# Hypnos_V3_2.net
KiCad netlist of a schematic drawn in EAGLE
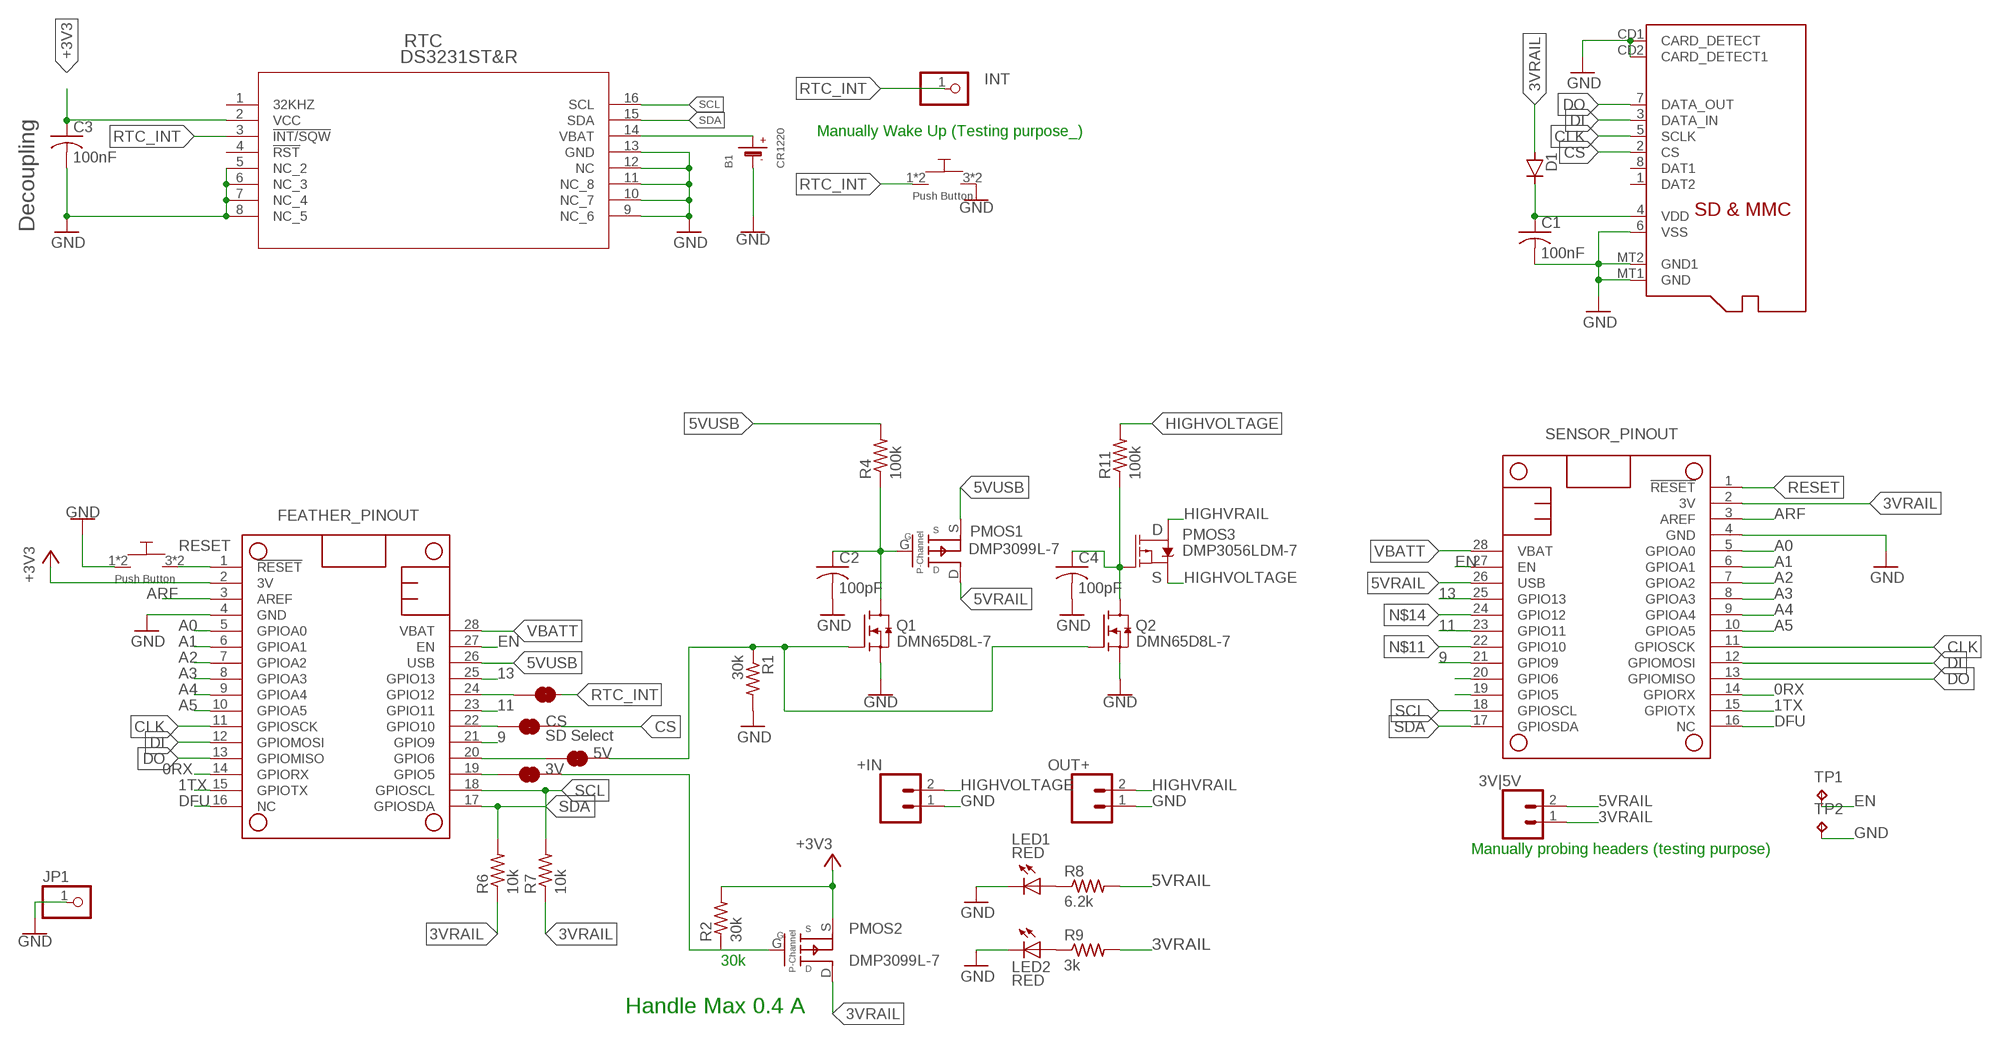
[diagram p0: schematic, sheet 1]

(export (version "E")
  (design (tool "Eeschema 10.0.6"))
  (components
    (comp (ref "+IN")
      (value "HIGHV-IN")
      (footprint "eagle-import:1X02_NO_SILK")
      (libsource (lib "eagle-import") (part "CONN_021X02_NO_SILK"))
    )
    (comp (ref "3V")
      (value "JUMPER-SMT_2_NC_TRACE_SILK")
      (footprint "eagle-import:SMT-JUMPER_2_NC_TRACE_SILK")
      (libsource (lib "eagle-import") (part "JUMPER-SMT_2_NC_TRACE_SILK"))
    )
    (comp (ref "3V|5V")
      (value "CONN_021X02_NO_SILK")
      (footprint "eagle-import:1X02_NO_SILK")
      (libsource (lib "eagle-import") (part "CONN_021X02_NO_SILK"))
    )
    (comp (ref "5V")
      (value "JUMPER-SMT_2_NC_TRACE_SILK")
      (footprint "eagle-import:SMT-JUMPER_2_NC_TRACE_SILK")
      (libsource (lib "eagle-import") (part "JUMPER-SMT_2_NC_TRACE_SILK"))
    )
    (comp (ref "B1")
      (value "CR1220")
      (footprint "eagle-import:CR1220")
      (libsource (lib "eagle-import") (part "BATTERYCR1220_SMT"))
    )
    (comp (ref "C1")
      (value "100nF")
      (footprint "eagle-import:C1206")
      (libsource (lib "eagle-import") (part "C-USC1206"))
    )
    (comp (ref "C2")
      (value "100pF")
      (footprint "eagle-import:C0805")
      (libsource (lib "eagle-import") (part "resistor_348_C-USC0805"))
    )
    (comp (ref "C3")
      (value "100nF")
      (footprint "eagle-import:C1206")
      (libsource (lib "eagle-import") (part "C-USC1206"))
    )
    (comp (ref "C4")
      (value "100pF")
      (footprint "eagle-import:C0805")
      (libsource (lib "eagle-import") (part "resistor_348_C-USC0805"))
    )
    (comp (ref "CS")
      (value "SD Select")
      (footprint "eagle-import:SMT-JUMPER_2_NC_TRACE_SILK")
      (libsource (lib "eagle-import") (part "JUMPER-SMT_2_NC_TRACE_SILK"))
    )
    (comp (ref "D1")
      (value "D-SOD123")
      (footprint "eagle-import:SOD123")
      (libsource (lib "eagle-import") (part "D-SOD123"))
    )
    (comp (ref "FEATHERWING")
      (value "SENSOR_PINOUT")
      (footprint "eagle-import:FEATHERWING")
      (libsource (lib "eagle-import") (part "powerboard_FEATHERWING"))
    )
    (comp (ref "INT")
      (value "PINHD-1X1CB")
      (footprint "eagle-import:1X01-CLEANBIG")
      (libsource (lib "eagle-import") (part "PINHD-1X1CB"))
    )
    (comp (ref "JP1")
      (value "PINHD-1X1CB")
      (footprint "eagle-import:1X01-CLEANBIG")
      (libsource (lib "eagle-import") (part "PINHD-1X1CB"))
    )
    (comp (ref "LED1")
      (value "RED")
      (footprint "eagle-import:CHIPLED_0805")
      (libsource (lib "eagle-import") (part "LEDCHIPLED_0805"))
    )
    (comp (ref "LED2")
      (value "RED")
      (footprint "eagle-import:CHIPLED_0805")
      (libsource (lib "eagle-import") (part "LEDCHIPLED_0805"))
    )
    (comp (ref "MICROSD")
      (value "MICROSD")
      (footprint "eagle-import:MICROSD")
      (libsource (lib "eagle-import") (part "MICROSD"))
    )
    (comp (ref "MS2")
      (value "FEATHER_PINOUT")
      (footprint "eagle-import:FEATHERWING")
      (libsource (lib "eagle-import") (part "FEATHERWING"))
    )
    (comp (ref "OUT+")
      (value "HIGHV-OUT")
      (footprint "eagle-import:1X02_NO_SILK")
      (libsource (lib "eagle-import") (part "CONN_021X02_NO_SILK"))
    )
    (comp (ref "PMOS1")
      (value "DMP3099L-7")
      (footprint "eagle-import:SOT-23-3")
      (libsource (lib "eagle-import") (part "SSM3J3228R"))
    )
    (comp (ref "PMOS2")
      (value "DMP3099L-7")
      (footprint "eagle-import:SOT-23-3")
      (libsource (lib "eagle-import") (part "SSM3J3228R"))
    )
    (comp (ref "PMOS3")
      (value "DMP3056LDM-7")
      (footprint "eagle-import:SOT23-6")
      (libsource (lib "eagle-import") (part "P-MOSFET"))
    )
    (comp (ref "Q1")
      (value "DMN65D8L-7")
      (footprint "eagle-import:SOT23-S")
      (libsource (lib "eagle-import") (part "NMOS"))
    )
    (comp (ref "Q2")
      (value "DMN65D8L-7")
      (footprint "eagle-import:SOT23-S")
      (libsource (lib "eagle-import") (part "NMOS"))
    )
    (comp (ref "R1")
      (value "30k")
      (footprint "eagle-import:RES_1206")
      (fields
        (field (name "DIGIKEY_PART_NUMBER") "WSLP-.05TR-ND")
        (field (name "MANUFACTURER") "Vishay Dale")
        (field (name "MPN") "WSLP1206R0500FEA")
        (field (name "CREATED_BY") "PCBLayout.com")
      )
      (libsource (lib "eagle-import") (part "WSLP1206R0500FEA"))
    )
    (comp (ref "R2")
      (value "30k")
      (footprint "eagle-import:RES_1206")
      (fields
        (field (name "DIGIKEY_PART_NUMBER") "WSLP-.05TR-ND")
        (field (name "MANUFACTURER") "Vishay Dale")
        (field (name "MPN") "WSLP1206R0500FEA")
        (field (name "CREATED_BY") "PCBLayout.com")
      )
      (libsource (lib "eagle-import") (part "WSLP1206R0500FEA"))
    )
    (comp (ref "R4")
      (value "100k")
      (footprint "eagle-import:RES_1206")
      (fields
        (field (name "DIGIKEY_PART_NUMBER") "WSLP-.05TR-ND")
        (field (name "MANUFACTURER") "Vishay Dale")
        (field (name "MPN") "WSLP1206R0500FEA")
        (field (name "CREATED_BY") "PCBLayout.com")
      )
      (libsource (lib "eagle-import") (part "WSLP1206R0500FEA"))
    )
    (comp (ref "R6")
      (value "10k")
      (footprint "eagle-import:RES_1206")
      (fields
        (field (name "DIGIKEY_PART_NUMBER") "WSLP-.05TR-ND")
        (field (name "MANUFACTURER") "Vishay Dale")
        (field (name "MPN") "WSLP1206R0500FEA")
        (field (name "CREATED_BY") "PCBLayout.com")
      )
      (libsource (lib "eagle-import") (part "WSLP1206R0500FEA"))
    )
    (comp (ref "R7")
      (value "10k")
      (footprint "eagle-import:RES_1206")
      (fields
        (field (name "DIGIKEY_PART_NUMBER") "WSLP-.05TR-ND")
        (field (name "MANUFACTURER") "Vishay Dale")
        (field (name "MPN") "WSLP1206R0500FEA")
        (field (name "CREATED_BY") "PCBLayout.com")
      )
      (libsource (lib "eagle-import") (part "WSLP1206R0500FEA"))
    )
    (comp (ref "R8")
      (value "6.2k")
      (footprint "eagle-import:RES_1206")
      (fields
        (field (name "DIGIKEY_PART_NUMBER") "WSLP-.05TR-ND")
        (field (name "MANUFACTURER") "Vishay Dale")
        (field (name "MPN") "WSLP1206R0500FEA")
        (field (name "CREATED_BY") "PCBLayout.com")
      )
      (libsource (lib "eagle-import") (part "WSLP1206R0500FEA"))
    )
    (comp (ref "R9")
      (value "3k")
      (footprint "eagle-import:RES_1206")
      (fields
        (field (name "DIGIKEY_PART_NUMBER") "WSLP-.05TR-ND")
        (field (name "MANUFACTURER") "Vishay Dale")
        (field (name "MPN") "WSLP1206R0500FEA")
        (field (name "CREATED_BY") "PCBLayout.com")
      )
      (libsource (lib "eagle-import") (part "WSLP1206R0500FEA"))
    )
    (comp (ref "R11")
      (value "100k")
      (footprint "eagle-import:RES_1206")
      (fields
        (field (name "DIGIKEY_PART_NUMBER") "WSLP-.05TR-ND")
        (field (name "MANUFACTURER") "Vishay Dale")
        (field (name "MPN") "WSLP1206R0500FEA")
        (field (name "CREATED_BY") "PCBLayout.com")
      )
      (libsource (lib "eagle-import") (part "WSLP1206R0500FEA"))
    )
    (comp (ref "RTC")
      (value "DS3231ST&R")
      (footprint "eagle-import:21-0042B_16")
      (fields (field (name "MANUFACTURER_PART_NUMBER") "DS3231S#T&R"))
      (libsource (lib "eagle-import") (part "DS3231ST&R"))
    )
    (comp (ref "RTC_INT")
      (value "JUMPER-SMT_2_NC_TRACE_SILK")
      (footprint "eagle-import:SMT-JUMPER_2_NC_TRACE_SILK")
      (libsource (lib "eagle-import") (part "JUMPER-SMT_2_NC_TRACE_SILK"))
    )
    (comp (ref "TP1")
      (value "TPTP16R")
      (footprint "eagle-import:TP16R")
      (libsource (lib "eagle-import") (part "TPTP16R"))
    )
    (comp (ref "TP2")
      (value "TPTP16R")
      (footprint "eagle-import:TP16R")
      (libsource (lib "eagle-import") (part "TPTP16R"))
    )
    (comp (ref "U$1")
      (value "PUSH_BUTTON")
      (footprint "eagle-import:PUSHBUTTON_SMD")
      (libsource (lib "eagle-import") (part "PUSH_BUTTON"))
    )
    (comp (ref "U$2")
      (value "PUSH_BUTTON")
      (footprint "eagle-import:PUSHBUTTON_SMD")
      (libsource (lib "eagle-import") (part "PUSH_BUTTON"))
    )
  )
  (nets
    (net (code "1") (name "+3V3") (class "Default")
      (node (ref "C3") (pin "1") (pinfunction "1_1") (pintype "passive"))
      (node (ref "MS2") (pin "2") (pinfunction "3V_2") (pintype "power_in"))
      (node (ref "PMOS2") (pin "S") (pinfunction "S_S") (pintype "bidirectional"))
      (node (ref "R2") (pin "2") (pinfunction "2_2") (pintype "passive"))
      (node (ref "RTC") (pin "2") (pinfunction "VCC_2") (pintype "power_in"))
    )
    (net (code "2") (name "/0RX") (class "Default")
      (node (ref "FEATHERWING") (pin "14") (pinfunction "GPIORX_14") (pintype "bidirectional"))
      (node (ref "MS2") (pin "14") (pinfunction "GPIORX_14") (pintype "bidirectional"))
    )
    (net (code "3") (name "/1TX") (class "Default")
      (node (ref "FEATHERWING") (pin "15") (pinfunction "GPIOTX_15") (pintype "bidirectional"))
      (node (ref "MS2") (pin "15") (pinfunction "GPIOTX_15") (pintype "bidirectional"))
    )
    (net (code "4") (name "/9") (class "Default")
      (node (ref "FEATHERWING") (pin "21") (pinfunction "GPIO9_21") (pintype "bidirectional"))
      (node (ref "MS2") (pin "21") (pinfunction "GPIO9_21") (pintype "bidirectional"))
    )
    (net (code "5") (name "/11") (class "Default")
      (node (ref "FEATHERWING") (pin "23") (pinfunction "GPIO11_23") (pintype "bidirectional"))
      (node (ref "MS2") (pin "23") (pinfunction "GPIO11_23") (pintype "bidirectional"))
    )
    (net (code "6") (name "/13") (class "Default")
      (node (ref "FEATHERWING") (pin "25") (pinfunction "GPIO13_25") (pintype "bidirectional"))
      (node (ref "MS2") (pin "25") (pinfunction "GPIO13_25") (pintype "bidirectional"))
    )
    (net (code "7") (name "/A0") (class "Default")
      (node (ref "FEATHERWING") (pin "5") (pinfunction "GPIOA0_5") (pintype "bidirectional"))
      (node (ref "MS2") (pin "5") (pinfunction "GPIOA0_5") (pintype "bidirectional"))
    )
    (net (code "8") (name "/A1") (class "Default")
      (node (ref "FEATHERWING") (pin "6") (pinfunction "GPIOA1_6") (pintype "bidirectional"))
      (node (ref "MS2") (pin "6") (pinfunction "GPIOA1_6") (pintype "bidirectional"))
    )
    (net (code "9") (name "/A2") (class "Default")
      (node (ref "FEATHERWING") (pin "7") (pinfunction "GPIOA2_7") (pintype "bidirectional"))
      (node (ref "MS2") (pin "7") (pinfunction "GPIOA2_7") (pintype "bidirectional"))
    )
    (net (code "10") (name "/A3") (class "Default")
      (node (ref "FEATHERWING") (pin "8") (pinfunction "GPIOA3_8") (pintype "bidirectional"))
      (node (ref "MS2") (pin "8") (pinfunction "GPIOA3_8") (pintype "bidirectional"))
    )
    (net (code "11") (name "/A4") (class "Default")
      (node (ref "FEATHERWING") (pin "9") (pinfunction "GPIOA4_9") (pintype "bidirectional"))
      (node (ref "MS2") (pin "9") (pinfunction "GPIOA4_9") (pintype "bidirectional"))
    )
    (net (code "12") (name "/A5") (class "Default")
      (node (ref "FEATHERWING") (pin "10") (pinfunction "GPIOA5_10") (pintype "bidirectional"))
      (node (ref "MS2") (pin "10") (pinfunction "GPIOA5_10") (pintype "bidirectional"))
    )
    (net (code "13") (name "/ARF") (class "Default")
      (node (ref "FEATHERWING") (pin "3") (pinfunction "AREF_3") (pintype "passive"))
      (node (ref "MS2") (pin "3") (pinfunction "AREF_3") (pintype "passive"))
    )
    (net (code "14") (name "/DFU") (class "Default")
      (node (ref "FEATHERWING") (pin "16") (pinfunction "NC_16") (pintype "passive"))
      (node (ref "MS2") (pin "16") (pinfunction "NC_16") (pintype "passive"))
    )
    (net (code "15") (name "/EN") (class "Default")
      (node (ref "FEATHERWING") (pin "27") (pinfunction "EN_27") (pintype "passive"))
      (node (ref "MS2") (pin "27") (pinfunction "EN_27") (pintype "passive"))
      (node (ref "TP1") (pin "TP") (pinfunction "TP_TP") (pintype "input"))
    )
    (net (code "16") (name "/HIGHVRAIL") (class "Default")
      (node (ref "OUT+") (pin "2") (pinfunction "2_2") (pintype "passive"))
      (node (ref "PMOS3") (pin "1") (pinfunction "D_1") (pintype "bidirectional"))
      (node (ref "PMOS3") (pin "2") (pinfunction "D_2") (pintype "bidirectional"))
      (node (ref "PMOS3") (pin "5") (pinfunction "D_5") (pintype "bidirectional"))
      (node (ref "PMOS3") (pin "6") (pinfunction "D_6") (pintype "bidirectional"))
    )
    (net (code "17") (name "3VRAIL") (class "Default")
      (node (ref "3V|5V") (pin "1") (pinfunction "1_1") (pintype "passive"))
      (node (ref "D1") (pin "2") (pinfunction "A_2") (pintype "passive"))
      (node (ref "FEATHERWING") (pin "2") (pinfunction "3V_2") (pintype "power_in"))
      (node (ref "PMOS2") (pin "D") (pinfunction "D_D") (pintype "bidirectional"))
      (node (ref "R6") (pin "1") (pinfunction "1_1") (pintype "passive"))
      (node (ref "R7") (pin "1") (pinfunction "1_1") (pintype "passive"))
      (node (ref "R9") (pin "2") (pinfunction "2_2") (pintype "passive"))
    )
    (net (code "18") (name "5VRAIL") (class "Default")
      (node (ref "3V|5V") (pin "2") (pinfunction "2_2") (pintype "passive"))
      (node (ref "FEATHERWING") (pin "26") (pinfunction "USB_26") (pintype "power_in"))
      (node (ref "PMOS1") (pin "D") (pinfunction "D_D") (pintype "bidirectional"))
      (node (ref "R8") (pin "2") (pinfunction "2_2") (pintype "passive"))
    )
    (net (code "19") (name "5VUSB") (class "Default")
      (node (ref "MS2") (pin "26") (pinfunction "USB_26") (pintype "power_in"))
      (node (ref "PMOS1") (pin "S") (pinfunction "S_S") (pintype "bidirectional"))
      (node (ref "R4") (pin "2") (pinfunction "2_2") (pintype "passive"))
    )
    (net (code "20") (name "CLK") (class "Default")
      (node (ref "FEATHERWING") (pin "11") (pinfunction "GPIOSCK_11") (pintype "bidirectional"))
      (node (ref "MICROSD") (pin "5") (pinfunction "SCLK_5") (pintype "input"))
      (node (ref "MS2") (pin "11") (pinfunction "GPIOSCK_11") (pintype "bidirectional"))
    )
    (net (code "21") (name "CS") (class "Default")
      (node (ref "CS") (pin "2") (pinfunction "2_2") (pintype "passive"))
      (node (ref "MICROSD") (pin "2") (pinfunction "CS_2") (pintype "input"))
    )
    (net (code "22") (name "DI") (class "Default")
      (node (ref "FEATHERWING") (pin "12") (pinfunction "GPIOMOSI_12") (pintype "bidirectional"))
      (node (ref "MICROSD") (pin "3") (pinfunction "DATA_IN_3") (pintype "input"))
      (node (ref "MS2") (pin "12") (pinfunction "GPIOMOSI_12") (pintype "bidirectional"))
    )
    (net (code "23") (name "DO") (class "Default")
      (node (ref "FEATHERWING") (pin "13") (pinfunction "GPIOMISO_13") (pintype "bidirectional"))
      (node (ref "MICROSD") (pin "7") (pinfunction "DATA_OUT_7") (pintype "output"))
      (node (ref "MS2") (pin "13") (pinfunction "GPIOMISO_13") (pintype "bidirectional"))
    )
    (net (code "24") (name "GND") (class "Default")
      (node (ref "+IN") (pin "1") (pinfunction "1_1") (pintype "passive"))
      (node (ref "B1") (pin "-") (pinfunction "-_-") (pintype "passive"))
      (node (ref "C1") (pin "2") (pinfunction "2_2") (pintype "passive"))
      (node (ref "C2") (pin "2") (pinfunction "2_2") (pintype "passive"))
      (node (ref "C3") (pin "2") (pinfunction "2_2") (pintype "passive"))
      (node (ref "C4") (pin "2") (pinfunction "2_2") (pintype "passive"))
      (node (ref "FEATHERWING") (pin "4") (pinfunction "GND_4") (pintype "power_in"))
      (node (ref "JP1") (pin "1") (pinfunction "1_1") (pintype "passive"))
      (node (ref "LED1") (pin "C") (pinfunction "C_C") (pintype "passive"))
      (node (ref "LED2") (pin "C") (pinfunction "C_C") (pintype "passive"))
      (node (ref "MICROSD") (pin "6") (pinfunction "VSS_6") (pintype "power_in"))
      (node (ref "MICROSD") (pin "CD1") (pinfunction "CARD_DETECT_CD1") (pintype "passive"))
      (node (ref "MICROSD") (pin "CD2") (pinfunction "CARD_DETECT1_CD2") (pintype "passive"))
      (node (ref "MICROSD") (pin "MT1") (pinfunction "GND_MT1") (pintype "power_in"))
      (node (ref "MICROSD") (pin "MT2") (pinfunction "GND1_MT2") (pintype "power_in"))
      (node (ref "MS2") (pin "4") (pinfunction "GND_4") (pintype "power_in"))
      (node (ref "OUT+") (pin "1") (pinfunction "1_1") (pintype "passive"))
      (node (ref "Q1") (pin "2") (pinfunction "S_2") (pintype "passive"))
      (node (ref "Q2") (pin "2") (pinfunction "S_2") (pintype "passive"))
      (node (ref "R1") (pin "2") (pinfunction "2_2") (pintype "passive"))
      (node (ref "RTC") (pin "10") (pinfunction "NC_7_10") (pintype "passive"))
      (node (ref "RTC") (pin "11") (pinfunction "NC_8_11") (pintype "passive"))
      (node (ref "RTC") (pin "12") (pinfunction "NC_12") (pintype "passive"))
      (node (ref "RTC") (pin "13") (pinfunction "GND_13") (pintype "power_in"))
      (node (ref "RTC") (pin "5") (pinfunction "NC_2_5") (pintype "passive"))
      (node (ref "RTC") (pin "6") (pinfunction "NC_3_6") (pintype "passive"))
      (node (ref "RTC") (pin "7") (pinfunction "NC_4_7") (pintype "passive"))
      (node (ref "RTC") (pin "8") (pinfunction "NC_5_8") (pintype "passive"))
      (node (ref "RTC") (pin "9") (pinfunction "NC_6_9") (pintype "passive"))
      (node (ref "TP2") (pin "TP") (pinfunction "TP_TP") (pintype "input"))
      (node (ref "U$1") (pin "1") (pinfunction "P$1_1") (pintype "bidirectional"))
      (node (ref "U$1") (pin "2") (pinfunction "P$1_2") (pintype "bidirectional"))
      (node (ref "U$2") (pin "3") (pinfunction "P$2_3") (pintype "bidirectional"))
      (node (ref "U$2") (pin "4") (pinfunction "P$2_4") (pintype "bidirectional"))
    )
    (net (code "25") (name "HIGHVOLTAGE") (class "Default")
      (node (ref "+IN") (pin "2") (pinfunction "2_2") (pintype "passive"))
      (node (ref "PMOS3") (pin "4") (pinfunction "S_4") (pintype "bidirectional"))
      (node (ref "R11") (pin "2") (pinfunction "2_2") (pintype "passive"))
    )
    (net (code "26") (name "N$11") (class "Default")
      (node (ref "CS") (pin "1") (pinfunction "1_1") (pintype "passive"))
      (node (ref "FEATHERWING") (pin "22") (pinfunction "GPIO10_22") (pintype "bidirectional"))
      (node (ref "MS2") (pin "22") (pinfunction "GPIO10_22") (pintype "bidirectional"))
    )
    (net (code "27") (name "N$14") (class "Default")
      (node (ref "FEATHERWING") (pin "24") (pinfunction "GPIO12_24") (pintype "bidirectional"))
      (node (ref "MS2") (pin "24") (pinfunction "GPIO12_24") (pintype "bidirectional"))
      (node (ref "RTC_INT") (pin "1") (pinfunction "1_1") (pintype "passive"))
    )
    (net (code "28") (name "Net-(3V-Pad2)") (class "Default")
      (node (ref "3V") (pin "2") (pinfunction "2_2") (pintype "passive"))
      (node (ref "PMOS2") (pin "G") (pinfunction "G_G") (pintype "bidirectional"))
      (node (ref "R2") (pin "1") (pinfunction "1_1") (pintype "passive"))
    )
    (net (code "29") (name "Net-(B1-+)") (class "Default")
      (node (ref "B1") (pin "+$1") (pinfunction "+_+$1") (pintype "passive"))
      (node (ref "RTC") (pin "14") (pinfunction "VBAT_14") (pintype "power_in"))
    )
    (net (code "30") (name "Net-(D1-C)") (class "Default")
      (node (ref "C1") (pin "1") (pinfunction "1_1") (pintype "passive"))
      (node (ref "D1") (pin "1") (pinfunction "C_1") (pintype "passive"))
      (node (ref "MICROSD") (pin "4") (pinfunction "VDD_4") (pintype "power_in"))
    )
    (net (code "31") (name "Net-(LED1-PadA)") (class "Default")
      (node (ref "LED1") (pin "A") (pinfunction "A_A") (pintype "passive"))
      (node (ref "R8") (pin "1") (pinfunction "1_1") (pintype "passive"))
    )
    (net (code "32") (name "Net-(LED2-PadA)") (class "Default")
      (node (ref "LED2") (pin "A") (pinfunction "A_A") (pintype "passive"))
      (node (ref "R9") (pin "1") (pinfunction "1_1") (pintype "passive"))
    )
    (net (code "33") (name "Net-(MS2-GPIO5)") (class "Default")
      (node (ref "3V") (pin "1") (pinfunction "1_1") (pintype "passive"))
      (node (ref "MS2") (pin "19") (pinfunction "GPIO5_19") (pintype "bidirectional"))
    )
    (net (code "34") (name "Net-(MS2-GPIO6)") (class "Default")
      (node (ref "5V") (pin "1") (pinfunction "1_1") (pintype "passive"))
      (node (ref "MS2") (pin "20") (pinfunction "GPIO6_20") (pintype "bidirectional"))
    )
    (net (code "35") (name "Net-(PMOS3-G)") (class "Default")
      (node (ref "C4") (pin "1") (pinfunction "1_1") (pintype "passive"))
      (node (ref "PMOS3") (pin "3") (pinfunction "G_3") (pintype "bidirectional"))
      (node (ref "Q2") (pin "3") (pinfunction "D_3") (pintype "passive"))
      (node (ref "R11") (pin "1") (pinfunction "1_1") (pintype "passive"))
    )
    (net (code "36") (name "Net-(Q1-D)") (class "Default")
      (node (ref "C2") (pin "1") (pinfunction "1_1") (pintype "passive"))
      (node (ref "PMOS1") (pin "G") (pinfunction "G_G") (pintype "bidirectional"))
      (node (ref "Q1") (pin "3") (pinfunction "D_3") (pintype "passive"))
      (node (ref "R4") (pin "1") (pinfunction "1_1") (pintype "passive"))
    )
    (net (code "37") (name "Net-(Q1-G)") (class "Default")
      (node (ref "5V") (pin "2") (pinfunction "2_2") (pintype "passive"))
      (node (ref "Q1") (pin "1") (pinfunction "G_1") (pintype "passive"))
      (node (ref "Q2") (pin "1") (pinfunction "G_1") (pintype "passive"))
      (node (ref "R1") (pin "1") (pinfunction "1_1") (pintype "passive"))
    )
    (net (code "38") (name "RESET") (class "Default")
      (node (ref "FEATHERWING") (pin "1") (pinfunction "~{RESET}_1") (pintype "input"))
      (node (ref "MS2") (pin "1") (pinfunction "~{RESET}_1") (pintype "input"))
      (node (ref "U$1") (pin "3") (pinfunction "P$2_3") (pintype "bidirectional"))
      (node (ref "U$1") (pin "4") (pinfunction "P$2_4") (pintype "bidirectional"))
    )
    (net (code "39") (name "RTC_INT") (class "Default")
      (node (ref "INT") (pin "1") (pinfunction "1_1") (pintype "passive"))
      (node (ref "RTC") (pin "3") (pinfunction "~{INT/SQW}_3") (pintype "passive"))
      (node (ref "RTC_INT") (pin "2") (pinfunction "2_2") (pintype "passive"))
      (node (ref "U$2") (pin "1") (pinfunction "P$1_1") (pintype "bidirectional"))
      (node (ref "U$2") (pin "2") (pinfunction "P$1_2") (pintype "bidirectional"))
    )
    (net (code "40") (name "SCL") (class "Default")
      (node (ref "FEATHERWING") (pin "18") (pinfunction "GPIOSCL_18") (pintype "bidirectional"))
      (node (ref "MS2") (pin "18") (pinfunction "GPIOSCL_18") (pintype "bidirectional"))
      (node (ref "R7") (pin "2") (pinfunction "2_2") (pintype "passive"))
      (node (ref "RTC") (pin "16") (pinfunction "SCL_16") (pintype "passive"))
    )
    (net (code "41") (name "SDA") (class "Default")
      (node (ref "FEATHERWING") (pin "17") (pinfunction "GPIOSDA_17") (pintype "bidirectional"))
      (node (ref "MS2") (pin "17") (pinfunction "GPIOSDA_17") (pintype "bidirectional"))
      (node (ref "R6") (pin "2") (pinfunction "2_2") (pintype "passive"))
      (node (ref "RTC") (pin "15") (pinfunction "SDA_15") (pintype "passive"))
    )
    (net (code "42") (name "VBATT") (class "Default")
      (node (ref "FEATHERWING") (pin "28") (pinfunction "VBAT_28") (pintype "power_in"))
      (node (ref "MS2") (pin "28") (pinfunction "VBAT_28") (pintype "power_in"))
    )
    (net (code "43") (name "unconnected-(FEATHERWING-GPIO5-Pad19)") (class "Default")
      (node (ref "FEATHERWING") (pin "19") (pinfunction "GPIO5_19") (pintype "bidirectional"))
    )
    (net (code "44") (name "unconnected-(FEATHERWING-GPIO6-Pad20)") (class "Default")
      (node (ref "FEATHERWING") (pin "20") (pinfunction "GPIO6_20") (pintype "bidirectional"))
    )
    (net (code "45") (name "unconnected-(MICROSD-DAT1-Pad8)") (class "Default")
      (node (ref "MICROSD") (pin "8") (pinfunction "DAT1_8") (pintype "bidirectional"))
    )
    (net (code "46") (name "unconnected-(MICROSD-DAT2-Pad1)") (class "Default")
      (node (ref "MICROSD") (pin "1") (pinfunction "DAT2_1") (pintype "bidirectional"))
    )
    (net (code "47") (name "unconnected-(RTC-32KHZ-Pad1)") (class "Default")
      (node (ref "RTC") (pin "1") (pinfunction "32KHZ_1") (pintype "passive"))
    )
    (net (code "48") (name "unconnected-(RTC-~{RST}-Pad4)") (class "Default")
      (node (ref "RTC") (pin "4") (pinfunction "~{RST}_4") (pintype "passive"))
    )
  )
)
